# sw8.net
KiCad netlist of a schematic drawn in EAGLE
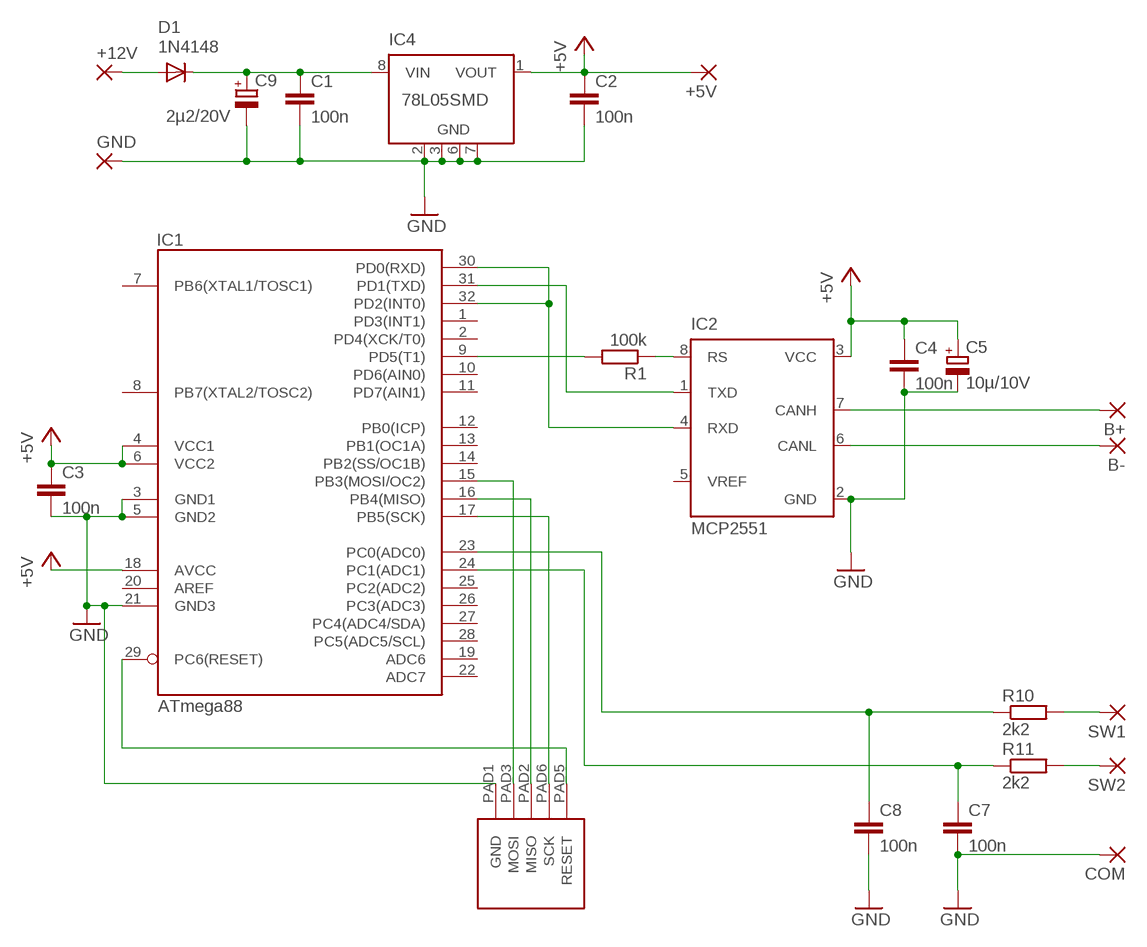
[diagram p0: schematic, sheet 1]

(export (version "E")
  (design (tool "Eeschema 10.0.6"))
  (components
    (comp (ref "+5V")
      (value "1,6/0,8")
      (footprint "eagle-import:1,6_0,8")
      (libsource (lib "eagle-import") (part "1,6/0,8"))
    )
    (comp (ref "+12V")
      (value "1,6/0,8")
      (footprint "eagle-import:1,6_0,8")
      (libsource (lib "eagle-import") (part "1,6/0,8"))
    )
    (comp (ref "B+")
      (value "1,6/0,8")
      (footprint "eagle-import:1,6_0,8")
      (libsource (lib "eagle-import") (part "1,6/0,8"))
    )
    (comp (ref "B-")
      (value "1,6/0,8")
      (footprint "eagle-import:1,6_0,8")
      (libsource (lib "eagle-import") (part "1,6/0,8"))
    )
    (comp (ref "C1")
      (value "100n")
      (footprint "eagle-import:C0603")
      (libsource (lib "eagle-import") (part "C-EUC0603"))
    )
    (comp (ref "C2")
      (value "100n")
      (footprint "eagle-import:C0603")
      (libsource (lib "eagle-import") (part "C-EUC0603"))
    )
    (comp (ref "C3")
      (value "100n")
      (footprint "eagle-import:C0603")
      (libsource (lib "eagle-import") (part "C-EUC0603"))
    )
    (comp (ref "C4")
      (value "100n")
      (footprint "eagle-import:C0603")
      (libsource (lib "eagle-import") (part "C-EUC0603"))
    )
    (comp (ref "C5")
      (value "10µ/10V")
      (footprint "eagle-import:A_3216-18W")
      (libsource (lib "eagle-import") (part "CPOL-EUA/3216-18W"))
    )
    (comp (ref "C7")
      (value "100n")
      (footprint "eagle-import:C0603")
      (libsource (lib "eagle-import") (part "C-EUC0603"))
    )
    (comp (ref "C8")
      (value "100n")
      (footprint "eagle-import:C0603")
      (libsource (lib "eagle-import") (part "C-EUC0603"))
    )
    (comp (ref "C9")
      (value "2µ2/20V")
      (footprint "eagle-import:A_3216-18W")
      (libsource (lib "eagle-import") (part "CPOL-EUA/3216-18W"))
    )
    (comp (ref "COM")
      (value "1,6/0,8")
      (footprint "eagle-import:1,6_0,8")
      (libsource (lib "eagle-import") (part "1,6/0,8"))
    )
    (comp (ref "D1")
      (value "1N4148")
      (footprint "eagle-import:SOD80C")
      (libsource (lib "eagle-import") (part "DIODE-SOD80C"))
    )
    (comp (ref "GND")
      (value "1,6/0,8")
      (footprint "eagle-import:1,6_0,8")
      (libsource (lib "eagle-import") (part "1,6/0,8"))
    )
    (comp (ref "IC1")
      (value "ATmega88")
      (footprint "eagle-import:TQFP32-08")
      (libsource (lib "eagle-import") (part "ATMEGA8"))
    )
    (comp (ref "IC2")
      (value "MCP2551")
      (footprint "eagle-import:SO8")
      (libsource (lib "eagle-import") (part "PCA82C250SMD"))
    )
    (comp (ref "IC4")
      (value "78L05SMD")
      (footprint "eagle-import:SO08")
      (libsource (lib "eagle-import") (part "78LSMD05"))
    )
    (comp (ref "R1")
      (value "100k")
      (footprint "eagle-import:R0603")
      (libsource (lib "eagle-import") (part "R-EU_R0603"))
    )
    (comp (ref "R10")
      (value "2k2")
      (footprint "eagle-import:R0603")
      (libsource (lib "eagle-import") (part "R-EU_R0603"))
    )
    (comp (ref "R11")
      (value "2k2")
      (footprint "eagle-import:R0603")
      (libsource (lib "eagle-import") (part "R-EU_R0603"))
    )
    (comp (ref "SW1")
      (value "1,6/0,8")
      (footprint "eagle-import:1,6_0,8")
      (libsource (lib "eagle-import") (part "1,6/0,8"))
    )
    (comp (ref "SW2")
      (value "1,6/0,8")
      (footprint "eagle-import:1,6_0,8")
      (libsource (lib "eagle-import") (part "1,6/0,8"))
    )
    (comp (ref "U$1")
      (value "ATMEL_ISP")
      (footprint "eagle-import:ATMEL_ISP")
      (libsource (lib "eagle-import") (part "ATMEL_ISP"))
    )
  )
  (nets
    (net (code "1") (name "+5V") (class "Default")
      (node (ref "+5V") (pin "1") (pinfunction "P_1") (pintype "passive"))
      (node (ref "C2") (pin "1") (pinfunction "1_1") (pintype "passive"))
      (node (ref "C3") (pin "1") (pinfunction "1_1") (pintype "passive"))
      (node (ref "C4") (pin "1") (pinfunction "1_1") (pintype "passive"))
      (node (ref "C5") (pin "+") (pinfunction "+_+") (pintype "passive"))
      (node (ref "IC1") (pin "18") (pinfunction "AVCC_18") (pintype "power_in"))
      (node (ref "IC1") (pin "4") (pinfunction "VCC1_4") (pintype "power_in"))
      (node (ref "IC1") (pin "6") (pinfunction "VCC2_6") (pintype "power_in"))
      (node (ref "IC2") (pin "3") (pinfunction "VCC_3") (pintype "power_in"))
      (node (ref "IC4") (pin "1") (pinfunction "VOUT_1") (pintype "output"))
    )
    (net (code "2") (name "/AREF") (class "Default")
      (node (ref "IC1") (pin "20") (pinfunction "AREF_20") (pintype "power_in"))
    )
    (net (code "3") (name "GND") (class "Default")
      (node (ref "C1") (pin "2") (pinfunction "2_2") (pintype "passive"))
      (node (ref "C2") (pin "2") (pinfunction "2_2") (pintype "passive"))
      (node (ref "C3") (pin "2") (pinfunction "2_2") (pintype "passive"))
      (node (ref "C4") (pin "2") (pinfunction "2_2") (pintype "passive"))
      (node (ref "C5") (pin "-") (pinfunction "-_-") (pintype "passive"))
      (node (ref "C7") (pin "2") (pinfunction "2_2") (pintype "passive"))
      (node (ref "C8") (pin "2") (pinfunction "2_2") (pintype "passive"))
      (node (ref "C9") (pin "-") (pinfunction "-_-") (pintype "passive"))
      (node (ref "COM") (pin "1") (pinfunction "P_1") (pintype "passive"))
      (node (ref "GND") (pin "1") (pinfunction "P_1") (pintype "passive"))
      (node (ref "IC1") (pin "21") (pinfunction "GND3_21") (pintype "power_in"))
      (node (ref "IC1") (pin "3") (pinfunction "GND1_3") (pintype "power_in"))
      (node (ref "IC1") (pin "5") (pinfunction "GND2_5") (pintype "power_in"))
      (node (ref "IC2") (pin "2") (pinfunction "GND_2") (pintype "power_in"))
      (node (ref "IC4") (pin "2") (pinfunction "GND_2") (pintype "power_in"))
      (node (ref "IC4") (pin "3") (pinfunction "GND_3") (pintype "power_in"))
      (node (ref "IC4") (pin "6") (pinfunction "GND_6") (pintype "power_in"))
      (node (ref "IC4") (pin "7") (pinfunction "GND_7") (pintype "power_in"))
      (node (ref "U$1") (pin "PAD1") (pinfunction "GND_PAD1") (pintype "power_in"))
    )
    (net (code "4") (name "Net-(+12V-P)") (class "Default")
      (node (ref "+12V") (pin "1") (pinfunction "P_1") (pintype "passive"))
      (node (ref "D1") (pin "A") (pinfunction "A_A") (pintype "passive"))
    )
    (net (code "5") (name "Net-(B+-P)") (class "Default")
      (node (ref "B+") (pin "1") (pinfunction "P_1") (pintype "passive"))
      (node (ref "IC2") (pin "7") (pinfunction "CANH_7") (pintype "bidirectional"))
    )
    (net (code "6") (name "Net-(B--P)") (class "Default")
      (node (ref "B-") (pin "1") (pinfunction "P_1") (pintype "passive"))
      (node (ref "IC2") (pin "6") (pinfunction "CANL_6") (pintype "bidirectional"))
    )
    (net (code "7") (name "Net-(IC1-PB3(MOSI{slash}OC2))") (class "Default")
      (node (ref "IC1") (pin "15") (pinfunction "PB3(MOSI/OC2)_15") (pintype "bidirectional"))
      (node (ref "U$1") (pin "PAD3") (pinfunction "MOSI_PAD3") (pintype "bidirectional"))
    )
    (net (code "8") (name "Net-(IC1-PB4(MISO))") (class "Default")
      (node (ref "IC1") (pin "16") (pinfunction "PB4(MISO)_16") (pintype "bidirectional"))
      (node (ref "U$1") (pin "PAD2") (pinfunction "MISO_PAD2") (pintype "bidirectional"))
    )
    (net (code "9") (name "Net-(IC1-PB5(SCK))") (class "Default")
      (node (ref "IC1") (pin "17") (pinfunction "PB5(SCK)_17") (pintype "bidirectional"))
      (node (ref "U$1") (pin "PAD6") (pinfunction "SCK_PAD6") (pintype "bidirectional"))
    )
    (net (code "10") (name "Net-(IC1-PC0(ADC0))") (class "Default")
      (node (ref "C8") (pin "1") (pinfunction "1_1") (pintype "passive"))
      (node (ref "IC1") (pin "23") (pinfunction "PC0(ADC0)_23") (pintype "bidirectional"))
      (node (ref "R10") (pin "1") (pinfunction "1_1") (pintype "passive"))
    )
    (net (code "11") (name "Net-(IC1-PC1(ADC1))") (class "Default")
      (node (ref "C7") (pin "1") (pinfunction "1_1") (pintype "passive"))
      (node (ref "IC1") (pin "24") (pinfunction "PC1(ADC1)_24") (pintype "bidirectional"))
      (node (ref "R11") (pin "1") (pinfunction "1_1") (pintype "passive"))
    )
    (net (code "12") (name "Net-(IC1-PC6(RESET))") (class "Default")
      (node (ref "IC1") (pin "29") (pinfunction "PC6(RESET)_29") (pintype "bidirectional"))
      (node (ref "U$1") (pin "PAD5") (pinfunction "RESET_PAD5") (pintype "bidirectional"))
    )
    (net (code "13") (name "Net-(IC1-PD0(RXD))") (class "Default")
      (node (ref "IC1") (pin "30") (pinfunction "PD0(RXD)_30") (pintype "bidirectional"))
      (node (ref "IC1") (pin "32") (pinfunction "PD2(INT0)_32") (pintype "bidirectional"))
      (node (ref "IC2") (pin "4") (pinfunction "RXD_4") (pintype "output"))
    )
    (net (code "14") (name "Net-(IC1-PD1(TXD))") (class "Default")
      (node (ref "IC1") (pin "31") (pinfunction "PD1(TXD)_31") (pintype "bidirectional"))
      (node (ref "IC2") (pin "1") (pinfunction "TXD_1") (pintype "input"))
    )
    (net (code "15") (name "Net-(IC1-PD5(T1))") (class "Default")
      (node (ref "IC1") (pin "9") (pinfunction "PD5(T1)_9") (pintype "bidirectional"))
      (node (ref "R1") (pin "2") (pinfunction "2_2") (pintype "passive"))
    )
    (net (code "16") (name "Net-(IC2-RS)") (class "Default")
      (node (ref "IC2") (pin "8") (pinfunction "RS_8") (pintype "input"))
      (node (ref "R1") (pin "1") (pinfunction "1_1") (pintype "passive"))
    )
    (net (code "17") (name "Net-(IC4A-VIN)") (class "Default")
      (node (ref "C1") (pin "1") (pinfunction "1_1") (pintype "passive"))
      (node (ref "C9") (pin "+") (pinfunction "+_+") (pintype "passive"))
      (node (ref "D1") (pin "C") (pinfunction "C_C") (pintype "passive"))
      (node (ref "IC4") (pin "8") (pinfunction "VIN_8") (pintype "passive"))
    )
    (net (code "18") (name "Net-(SW1-P)") (class "Default")
      (node (ref "R10") (pin "2") (pinfunction "2_2") (pintype "passive"))
      (node (ref "SW1") (pin "1") (pinfunction "P_1") (pintype "passive"))
    )
    (net (code "19") (name "Net-(SW2-P)") (class "Default")
      (node (ref "R11") (pin "2") (pinfunction "2_2") (pintype "passive"))
      (node (ref "SW2") (pin "1") (pinfunction "P_1") (pintype "passive"))
    )
    (net (code "20") (name "unconnected-(IC1-ADC6-Pad19)") (class "Default")
      (node (ref "IC1") (pin "19") (pinfunction "ADC6_19") (pintype "bidirectional"))
    )
    (net (code "21") (name "unconnected-(IC1-ADC7-Pad22)") (class "Default")
      (node (ref "IC1") (pin "22") (pinfunction "ADC7_22") (pintype "bidirectional"))
    )
    (net (code "22") (name "unconnected-(IC1-PB0(ICP)-Pad12)") (class "Default")
      (node (ref "IC1") (pin "12") (pinfunction "PB0(ICP)_12") (pintype "bidirectional"))
    )
    (net (code "23") (name "unconnected-(IC1-PB1(OC1A)-Pad13)") (class "Default")
      (node (ref "IC1") (pin "13") (pinfunction "PB1(OC1A)_13") (pintype "bidirectional"))
    )
    (net (code "24") (name "unconnected-(IC1-PB2(SS{slash}OC1B)-Pad14)") (class "Default")
      (node (ref "IC1") (pin "14") (pinfunction "PB2(SS/OC1B)_14") (pintype "bidirectional"))
    )
    (net (code "25") (name "unconnected-(IC1-PB6(XTAL1{slash}TOSC1)-Pad7)") (class "Default")
      (node (ref "IC1") (pin "7") (pinfunction "PB6(XTAL1/TOSC1)_7") (pintype "bidirectional"))
    )
    (net (code "26") (name "unconnected-(IC1-PB7(XTAL2{slash}TOSC2)-Pad8)") (class "Default")
      (node (ref "IC1") (pin "8") (pinfunction "PB7(XTAL2/TOSC2)_8") (pintype "bidirectional"))
    )
    (net (code "27") (name "unconnected-(IC1-PC2(ADC2)-Pad25)") (class "Default")
      (node (ref "IC1") (pin "25") (pinfunction "PC2(ADC2)_25") (pintype "bidirectional"))
    )
    (net (code "28") (name "unconnected-(IC1-PC3(ADC3)-Pad26)") (class "Default")
      (node (ref "IC1") (pin "26") (pinfunction "PC3(ADC3)_26") (pintype "bidirectional"))
    )
    (net (code "29") (name "unconnected-(IC1-PC4(ADC4{slash}SDA)-Pad27)") (class "Default")
      (node (ref "IC1") (pin "27") (pinfunction "PC4(ADC4/SDA)_27") (pintype "bidirectional"))
    )
    (net (code "30") (name "unconnected-(IC1-PC5(ADC5{slash}SCL)-Pad28)") (class "Default")
      (node (ref "IC1") (pin "28") (pinfunction "PC5(ADC5/SCL)_28") (pintype "bidirectional"))
    )
    (net (code "31") (name "unconnected-(IC1-PD3(INT1)-Pad1)") (class "Default")
      (node (ref "IC1") (pin "1") (pinfunction "PD3(INT1)_1") (pintype "bidirectional"))
    )
    (net (code "32") (name "unconnected-(IC1-PD4(XCK{slash}T0)-Pad2)") (class "Default")
      (node (ref "IC1") (pin "2") (pinfunction "PD4(XCK/T0)_2") (pintype "bidirectional"))
    )
    (net (code "33") (name "unconnected-(IC1-PD6(AIN0)-Pad10)") (class "Default")
      (node (ref "IC1") (pin "10") (pinfunction "PD6(AIN0)_10") (pintype "bidirectional"))
    )
    (net (code "34") (name "unconnected-(IC1-PD7(AIN1)-Pad11)") (class "Default")
      (node (ref "IC1") (pin "11") (pinfunction "PD7(AIN1)_11") (pintype "bidirectional"))
    )
    (net (code "35") (name "unconnected-(IC2-VREF-Pad5)") (class "Default")
      (node (ref "IC2") (pin "5") (pinfunction "VREF_5") (pintype "output"))
    )
  )
)
